# 13_Raspberry_Misc.net
KiCad netlist of a schematic drawn in Altium Designer
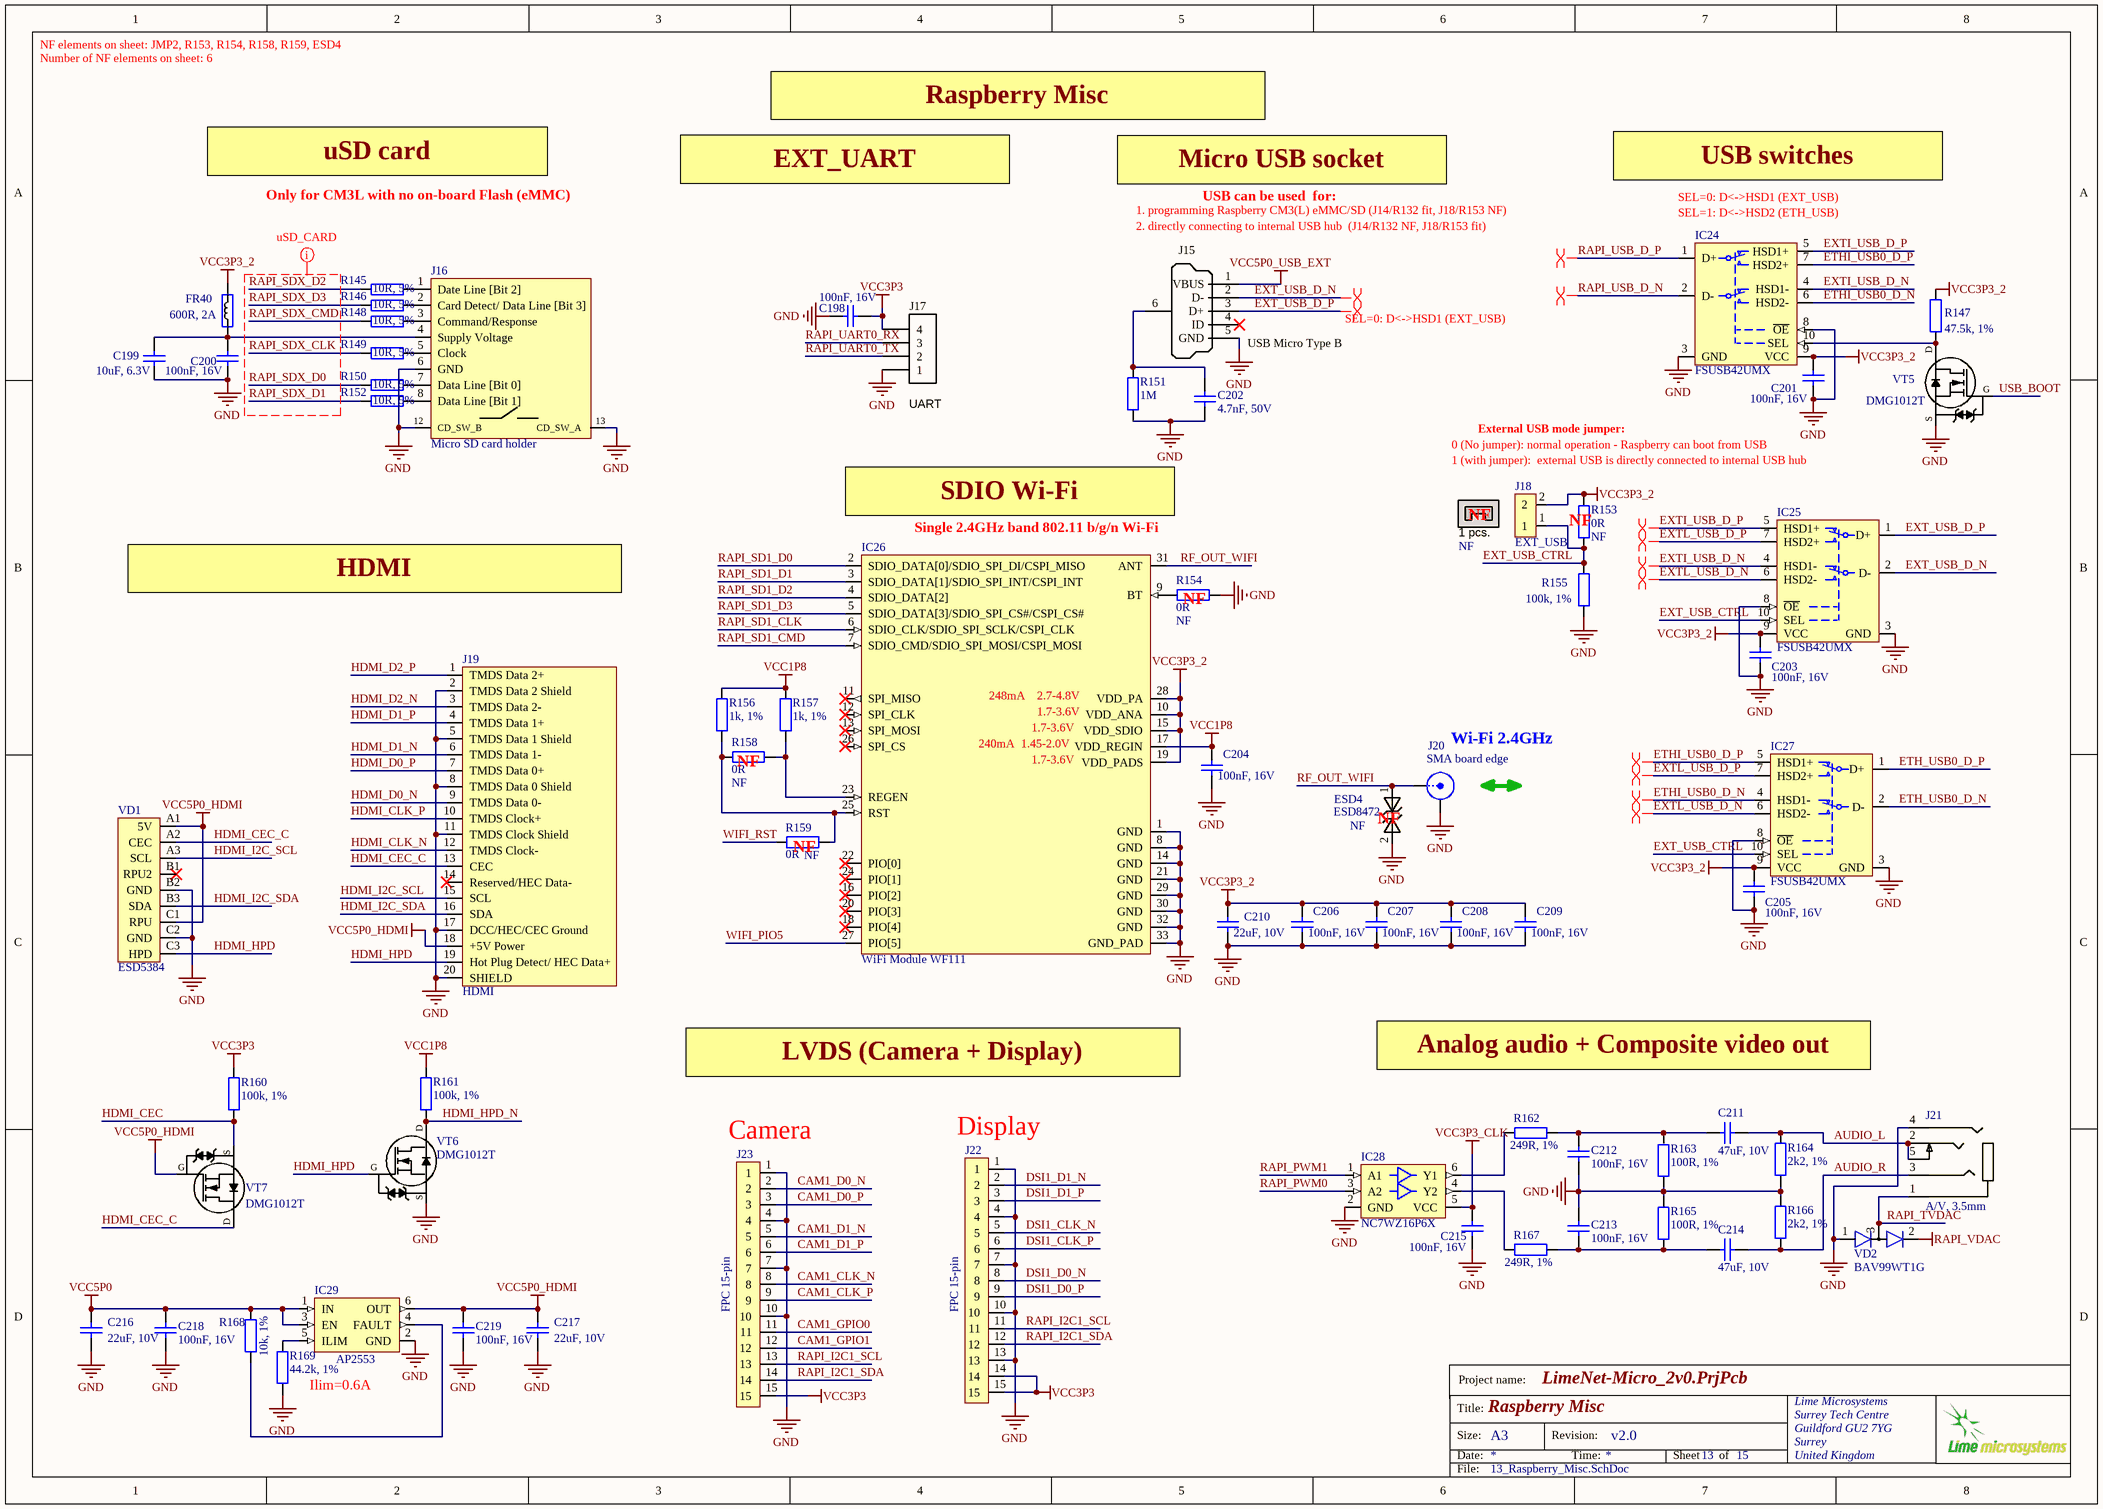
[diagram p0: 13_Raspberry_Misc.SchDoc]

(export (version "E")
  (design (tool "Eeschema 10.0.6"))
  (components
    (comp (ref "C198")
      (value "100nF, 16V")
      (footprint "CAP0402")
      (fields (field (name "TOLERANCE") "10 %") (field (name "MANUFACTURER") "Murata Electronics"))
      (libsource (lib "LimeFPGAboard_schLib") (part "Cap_0603"))
    )
    (comp (ref "C199")
      (value "10uF, 6.3V")
      (footprint "CAP0603")
      (fields (field (name "TOLERANCE") "±20%") (field (name "MANUFACTURER") "Yageo"))
      (libsource (lib "LimeFPGAboard_schLib") (part "Cap_0603"))
    )
    (comp (ref "C200")
      (value "100nF, 16V")
      (footprint "CAP0402")
      (fields (field (name "TOLERANCE") "10 %") (field (name "MANUFACTURER") "Murata Electronics"))
      (libsource (lib "LimeFPGAboard_schLib") (part "Cap_0603"))
    )
    (comp (ref "C201")
      (value "100nF, 16V")
      (footprint "CAP0402")
      (fields
        (field (name "MANUFACTURER") "Murata Electronics")
        (field (name "TOLERANCE") "10 %")
        (field (name "MANUFACTURER PART NUMBER") "GRM155R71C104KA88D")
      )
      (libsource (lib "LimeMicroAltiumLib_schLib") (part "Cap_0402"))
    )
    (comp (ref "C202")
      (value "4.7nF, 50V")
      (footprint "CAP0402")
      (fields
        (field (name "TOLERANCE") "±10%")
        (field (name "MANUFACTURER") "Murata Electronics North America")
      )
      (libsource (lib "LimeMicroAltiumLib_schLib") (part "Cap_0402"))
    )
    (comp (ref "C203")
      (value "100nF, 16V")
      (footprint "CAP0402")
      (fields
        (field (name "MANUFACTURER") "Murata Electronics")
        (field (name "TOLERANCE") "10 %")
        (field (name "MANUFACTURER PART NUMBER") "GRM155R71C104KA88D")
      )
      (libsource (lib "LimeMicroAltiumLib_schLib") (part "Cap_0402"))
    )
    (comp (ref "C204")
      (value "100nF, 16V")
      (footprint "CAP0402")
      (fields
        (field (name "MANUFACTURER") "Murata Electronics")
        (field (name "TOLERANCE") "10 %")
        (field (name "MANUFACTURER PART NUMBER") "GRM155R71C104KA88D")
      )
      (libsource (lib "LimeMicroAltiumLib_schLib") (part "Cap_0402"))
    )
    (comp (ref "C205")
      (value "100nF, 16V")
      (footprint "CAP0402")
      (fields
        (field (name "MANUFACTURER") "Murata Electronics")
        (field (name "TOLERANCE") "10 %")
        (field (name "MANUFACTURER PART NUMBER") "GRM155R71C104KA88D")
      )
      (libsource (lib "LimeMicroAltiumLib_schLib") (part "Cap_0402"))
    )
    (comp (ref "C206")
      (value "100nF, 16V")
      (footprint "CAP0402")
      (fields
        (field (name "MANUFACTURER") "Murata Electronics")
        (field (name "TOLERANCE") "10 %")
        (field (name "MANUFACTURER PART NUMBER") "GRM155R71C104KA88D")
      )
      (libsource (lib "LimeMicroAltiumLib_schLib") (part "Cap_0402"))
    )
    (comp (ref "C207")
      (value "100nF, 16V")
      (footprint "CAP0402")
      (fields
        (field (name "MANUFACTURER") "Murata Electronics")
        (field (name "TOLERANCE") "10 %")
        (field (name "MANUFACTURER PART NUMBER") "GRM155R71C104KA88D")
      )
      (libsource (lib "LimeMicroAltiumLib_schLib") (part "Cap_0402"))
    )
    (comp (ref "C208")
      (value "100nF, 16V")
      (footprint "CAP0402")
      (fields
        (field (name "MANUFACTURER") "Murata Electronics")
        (field (name "TOLERANCE") "10 %")
        (field (name "MANUFACTURER PART NUMBER") "GRM155R71C104KA88D")
      )
      (libsource (lib "LimeMicroAltiumLib_schLib") (part "Cap_0402"))
    )
    (comp (ref "C209")
      (value "100nF, 16V")
      (footprint "CAP0402")
      (fields
        (field (name "MANUFACTURER") "Murata Electronics")
        (field (name "TOLERANCE") "10 %")
        (field (name "MANUFACTURER PART NUMBER") "GRM155R71C104KA88D")
      )
      (libsource (lib "LimeMicroAltiumLib_schLib") (part "Cap_0402"))
    )
    (comp (ref "C210")
      (value "22uF, 10V")
      (footprint "CAP0603")
      (fields (field (name "TOLERANCE") "20 %") (field (name "MANUFACTURER") "TDK Corporation"))
      (libsource (lib "LimeFPGAboard_schLib") (part "Cap_0603"))
    )
    (comp (ref "C211")
      (value "47uF, 10V")
      (footprint "CAP1206")
      (fields (field (name "TOLERANCE") "±20%") (field (name "MANUFACTURER") "TDK Corporation"))
      (libsource (lib "LimeFPGAboard_schLib") (part "Cap_1206"))
    )
    (comp (ref "C212")
      (value "100nF, 16V")
      (footprint "CAP0402")
      (fields
        (field (name "MANUFACTURER") "Murata Electronics")
        (field (name "TOLERANCE") "10 %")
        (field (name "MANUFACTURER PART NUMBER") "GRM155R71C104KA88D")
      )
      (libsource (lib "LimeMicroAltiumLib_schLib") (part "Cap_0402"))
    )
    (comp (ref "C213")
      (value "100nF, 16V")
      (footprint "CAP0402")
      (fields
        (field (name "MANUFACTURER") "Murata Electronics")
        (field (name "TOLERANCE") "10 %")
        (field (name "MANUFACTURER PART NUMBER") "GRM155R71C104KA88D")
      )
      (libsource (lib "LimeMicroAltiumLib_schLib") (part "Cap_0402"))
    )
    (comp (ref "C214")
      (value "47uF, 10V")
      (footprint "CAP1206")
      (fields (field (name "TOLERANCE") "±20%") (field (name "MANUFACTURER") "TDK Corporation"))
      (libsource (lib "LimeFPGAboard_schLib") (part "Cap_1206"))
    )
    (comp (ref "C215")
      (value "100nF, 16V")
      (footprint "CAP0402")
      (fields
        (field (name "MANUFACTURER") "Murata Electronics")
        (field (name "TOLERANCE") "10 %")
        (field (name "MANUFACTURER PART NUMBER") "GRM155R71C104KA88D")
      )
      (libsource (lib "LimeMicroAltiumLib_schLib") (part "Cap_0402"))
    )
    (comp (ref "C216")
      (value "22uF, 10V")
      (footprint "CAP0603")
      (fields (field (name "TOLERANCE") "20 %") (field (name "MANUFACTURER") "TDK Corporation"))
      (libsource (lib "LimeFPGAboard_schLib") (part "Cap_0603"))
    )
    (comp (ref "C217")
      (value "22uF, 10V")
      (footprint "CAP0603")
      (fields (field (name "TOLERANCE") "20 %") (field (name "MANUFACTURER") "TDK Corporation"))
      (libsource (lib "LimeFPGAboard_schLib") (part "Cap_0603"))
    )
    (comp (ref "C218")
      (value "100nF, 16V")
      (footprint "CAP0402")
      (fields
        (field (name "MANUFACTURER") "Murata Electronics")
        (field (name "TOLERANCE") "10 %")
        (field (name "MANUFACTURER PART NUMBER") "GRM155R71C104KA88D")
      )
      (libsource (lib "LimeMicroAltiumLib_schLib") (part "Cap_0402"))
    )
    (comp (ref "C219")
      (value "100nF, 16V")
      (footprint "CAP0402")
      (fields
        (field (name "MANUFACTURER") "Murata Electronics")
        (field (name "TOLERANCE") "10 %")
        (field (name "MANUFACTURER PART NUMBER") "GRM155R71C104KA88D")
      )
      (libsource (lib "LimeMicroAltiumLib_schLib") (part "Cap_0402"))
    )
    (comp (ref "ESD4")
      (value "ESD8472")
      (footprint "ESD8472_X3DFN2")
      (fields
        (field (name "MANUFACTURER") "ON Semiconductor")
        (field (name "MANUFACTURER PART NUMBER") "ESD8472MUT5G")
        (field (name "ASSEMBLY INFO") "NF")
      )
      (libsource (lib "LimeMicroAltiumLib_schLib") (part "ESD8472"))
    )
    (comp (ref "FR40")
      (value "600R, 2A")
      (footprint "RES0805")
      (fields (field (name "MANUFACTURER") "TDK Corporation"))
      (libsource (lib "LimeMicroAltiumLib_schLib") (part "Ferrite"))
    )
    (comp (ref "IC24")
      (value "FSUSB42UMX")
      (footprint "FSUSB42UMX")
      (fields (field (name "MANUFACTURER") "ON Semiconductor") (field (name "BASE PART NUMBER") "FSUSB42"))
      (libsource (lib "LimeMicroAltiumLib_schLib_r01") (part "FSUSB42UMX"))
    )
    (comp (ref "IC25")
      (value "FSUSB42UMX")
      (footprint "FSUSB42UMX")
      (fields (field (name "MANUFACTURER") "ON Semiconductor") (field (name "BASE PART NUMBER") "FSUSB42"))
      (libsource (lib "") (part "FSUSB42UMX_1"))
    )
    (comp (ref "IC26")
      (value "WiFi Module WF111")
      (footprint "WF111-A-V1_WIFI")
      (fields (field (name "MANUFACTURER") "Bluegiga Technologies"))
      (libsource (lib "LimeMicroAltiumLib_schLib_r01") (part "WF111-A-V1_WIFI"))
    )
    (comp (ref "IC27")
      (value "FSUSB42UMX")
      (footprint "FSUSB42UMX")
      (fields (field (name "MANUFACTURER") "ON Semiconductor") (field (name "BASE PART NUMBER") "FSUSB42"))
      (libsource (lib "") (part "FSUSB42UMX_1"))
    )
    (comp (ref "IC28")
      (value "NC7WZ16P6X")
      (footprint "SC-70_NC7WZ16P6X")
      (fields (field (name "MANUFACTURER") "ON Semiconductor / Fairchild"))
      (libsource (lib "LimeMicroAltiumLib_schLib_r01") (part "NC7WZ16P6X_DUAL_BUFFER"))
    )
    (comp (ref "IC29")
      (value "AP2553")
      (footprint "SOT23-6")
      (fields (field (name "MANUFACTURER") "Diodes") (field (name "VOLTAGE") "5.5V"))
      (libsource (lib "LimeMicroAltiumLib_schLib_r01") (part "AP2553W6-7"))
    )
    (comp (ref "J15")
      (value "USB Micro Type B")
      (footprint "microUSB_v2")
      (description "Connector SMD USB Micro Type B")
      (fields (field (name "MANUFACTURER") "Amphenol FCI"))
      (libsource (lib "LimeMicroAltiumLib_schLib") (part "USB_Micro_TypeB"))
    )
    (comp (ref "J16")
      (value "Micro SD card holder")
      (footprint "MICRO_SD_CARD_114-00841-68_v2")
      (fields
        (field (name "MANUFACTURER") "Amphenol Commercial Products")
        (field (name "MANUFACTURER PART NUMBER") "114-00841-68")
      )
      (libsource (lib "LimeMicroAltiumLib_schLib_r01") (part "MICRO_SD_114-00841-68"))
    )
    (comp (ref "J17")
      (value "UART")
      (footprint "HEADER4X1_TH")
      (description "Header, 4-pin")
      (fields
        (field (name "MANUFACTURER") "Wurth Electronics Inc.")
        (field (name "MANUFACTURER PART NUMBER") "61300411121")
      )
      (libsource (lib "LimeMicroAltiumLib_schLib") (part "Header4P"))
    )
    (comp (ref "J18")
      (value "EXT_USB")
      (footprint "HDR_1x2")
      (fields (field (name "MANUFACTURER") "3M"))
      (libsource (lib "LimeFPGAboard_schLib") (part "Jumper"))
    )
    (comp (ref "J19")
      (value "HDMI")
      (footprint "HDMI_AMPHENOL_10029449-111RLF")
      (fields (field (name "MANUFACTURER") "Amphenol FCI"))
      (libsource (lib "LimeMicroAltiumLib_schLib_r01") (part "HDMI_AMPHENOL_10029449-111RLF"))
    )
    (comp (ref "J20")
      (value "SMA board edge")
      (footprint "SMA_connector_board_edge_SM")
      (description "CONN SMA JACK STR 50OHM EDGE MNT")
      (fields (field (name "MANUFACTURER") "RF Solutions"))
      (libsource (lib "LimeMicroAltiumLib_schLib") (part "RF_IF_connector"))
    )
    (comp (ref "J21")
      (value "A/V, 3.5mm")
      (footprint "Audio_jack_3.5mm")
      (fields (field (name "MANUFACTURER") "CUI Inc.") (field (name "MANUFACTURER PART NUMBER") "SJ-43515TS"))
      (libsource (lib "LimeMicroAltiumLib_schLib_r01") (part "AUDIO_JACK_3mm5_SJ-4351X"))
    )
    (comp (ref "J22")
      (value "FPC 15-pin")
      (footprint "FPC_CONNECTOR_15pin_1-1734248-5")
      (fields (field (name "MANUFACTURER") "TE Connectivity"))
      (libsource (lib "LimeMicroAltiumLib_schLib_r01") (part "FPC_CONNECTOR_15pin_1-1734248-5"))
    )
    (comp (ref "J23")
      (value "FPC 15-pin")
      (footprint "FPC_CONNECTOR_15pin_1-1734248-5")
      (fields (field (name "MANUFACTURER") "TE Connectivity"))
      (libsource (lib "LimeMicroAltiumLib_schLib_r01") (part "FPC_CONNECTOR_15pin_1-1734248-5"))
    )
    (comp (ref "JMP2")
      (value "1 pcs.")
      (description "Shorting Jumper, 2-position, 1.27mm pitch")
      (fields (field (name "ASSEMBLY INFO") "NF") (field (name "MANUFACTURER") "Sullins"))
      (libsource (lib "LimeMicroAltiumLib_schLib") (part "JUMP_2P_CONN_HEADER"))
    )
    (comp (ref "R145")
      (value "10R, 5%")
      (footprint "RES0402")
      (fields (field (name "TOLERANCE") "±5%") (field (name "MANUFACTURER") "Yageo"))
      (libsource (lib "LimeMicroAltiumLib_schLib") (part "Res_0402"))
    )
    (comp (ref "R146")
      (value "10R, 5%")
      (footprint "RES0402")
      (fields (field (name "TOLERANCE") "±5%") (field (name "MANUFACTURER") "Yageo"))
      (libsource (lib "LimeMicroAltiumLib_schLib") (part "Res_0402"))
    )
    (comp (ref "R147")
      (value "47.5k, 1%")
      (footprint "RES0402")
      (fields
        (field (name "MANUFACTURER PART NUMBER") "RC0402FR-0747K5L")
        (field (name "TOLERANCE") "±1%")
        (field (name "MANUFACTURER") "Yageo")
      )
      (libsource (lib "LimeMicroAltiumLib_schLib") (part "Res_0402"))
    )
    (comp (ref "R148")
      (value "10R, 5%")
      (footprint "RES0402")
      (fields (field (name "TOLERANCE") "±5%") (field (name "MANUFACTURER") "Yageo"))
      (libsource (lib "LimeMicroAltiumLib_schLib") (part "Res_0402"))
    )
    (comp (ref "R149")
      (value "10R, 5%")
      (footprint "RES0402")
      (fields (field (name "TOLERANCE") "±5%") (field (name "MANUFACTURER") "Yageo"))
      (libsource (lib "LimeMicroAltiumLib_schLib") (part "Res_0402"))
    )
    (comp (ref "R150")
      (value "10R, 5%")
      (footprint "RES0402")
      (fields (field (name "TOLERANCE") "±5%") (field (name "MANUFACTURER") "Yageo"))
      (libsource (lib "LimeMicroAltiumLib_schLib") (part "Res_0402"))
    )
    (comp (ref "R151")
      (value "1M")
      (footprint "RES0402")
      (fields (field (name "MANUFACTURER") "TE CONNECTIVITY"))
      (libsource (lib "LimeMicroAltiumLib_schLib") (part "Res_0402"))
    )
    (comp (ref "R152")
      (value "10R, 5%")
      (footprint "RES0402")
      (fields (field (name "TOLERANCE") "±5%") (field (name "MANUFACTURER") "Yageo"))
      (libsource (lib "LimeMicroAltiumLib_schLib") (part "Res_0402"))
    )
    (comp (ref "R153")
      (value "0R")
      (footprint "RES0402")
      (fields
        (field (name "ASSEMBLY INFO") "NF")
        (field (name "MANUFACTURER") "Yageo")
        (field (name "TOLERANCE") "Jumper")
      )
      (libsource (lib "LimeMicroAltiumLib_schLib") (part "Res_0402"))
    )
    (comp (ref "R154")
      (value "0R")
      (footprint "RES0402")
      (fields
        (field (name "ASSEMBLY INFO") "NF")
        (field (name "MANUFACTURER") "Yageo")
        (field (name "TOLERANCE") "Jumper")
      )
      (libsource (lib "LimeMicroAltiumLib_schLib") (part "Res_0402"))
    )
    (comp (ref "R155")
      (value "100k, 1%")
      (footprint "RES0402")
      (fields
        (field (name "MANUFACTURER") "Vishay Dale")
        (field (name "TOLERANCE") "±1%")
        (field (name "MANUFACTURER PART NUMBER") "CRCW0402100KFKEDC")
      )
      (libsource (lib "LimeMicroAltiumLib_schLib") (part "Res_0402"))
    )
    (comp (ref "R156")
      (value "1k, 1%")
      (footprint "RES0402")
      (fields (field (name "MANUFACTURER") "Stackpole Electronics Inc") (field (name "TOLERANCE") "±1%"))
      (libsource (lib "LimeMicroAltiumLib_schLib") (part "Res_0402"))
    )
    (comp (ref "R157")
      (value "1k, 1%")
      (footprint "RES0402")
      (fields (field (name "MANUFACTURER") "Stackpole Electronics Inc") (field (name "TOLERANCE") "±1%"))
      (libsource (lib "LimeMicroAltiumLib_schLib") (part "Res_0402"))
    )
    (comp (ref "R158")
      (value "0R")
      (footprint "RES0402")
      (fields
        (field (name "ASSEMBLY INFO") "NF")
        (field (name "MANUFACTURER") "Yageo")
        (field (name "TOLERANCE") "Jumper")
      )
      (libsource (lib "LimeMicroAltiumLib_schLib") (part "Res_0402"))
    )
    (comp (ref "R159")
      (value "0R")
      (footprint "RES0402")
      (fields
        (field (name "ASSEMBLY INFO") "NF")
        (field (name "MANUFACTURER") "Yageo")
        (field (name "TOLERANCE") "Jumper")
      )
      (libsource (lib "LimeMicroAltiumLib_schLib") (part "Res_0402"))
    )
    (comp (ref "R160")
      (value "100k, 1%")
      (footprint "RES0402")
      (fields
        (field (name "MANUFACTURER") "Vishay Dale")
        (field (name "TOLERANCE") "±1%")
        (field (name "MANUFACTURER PART NUMBER") "CRCW0402100KFKEDC")
      )
      (libsource (lib "LimeMicroAltiumLib_schLib") (part "Res_0402"))
    )
    (comp (ref "R161")
      (value "100k, 1%")
      (footprint "RES0402")
      (fields
        (field (name "MANUFACTURER") "Vishay Dale")
        (field (name "TOLERANCE") "±1%")
        (field (name "MANUFACTURER PART NUMBER") "CRCW0402100KFKEDC")
      )
      (libsource (lib "LimeMicroAltiumLib_schLib") (part "Res_0402"))
    )
    (comp (ref "R162")
      (value "249R, 1%")
      (footprint "RES0402")
      (fields (field (name "MANUFACTURER") "Stackpole Electronics Inc") (field (name "TOLERANCE") "±1%"))
      (libsource (lib "LimeMicroAltiumLib_schLib") (part "Res_0402"))
    )
    (comp (ref "R163")
      (value "100R, 1%")
      (footprint "RES0402")
      (fields (field (name "TOLERANCE") "±1%") (field (name "MANUFACTURER") "Stackpole Electronics Inc."))
      (libsource (lib "LimeMicroAltiumLib_schLib") (part "Res_0402"))
    )
    (comp (ref "R164")
      (value "2k2, 1%")
      (footprint "RES0402")
      (fields (field (name "MANUFACTURER") "Stackpole Electronics Inc") (field (name "TOLERANCE") "±1%"))
      (libsource (lib "LimeMicroAltiumLib_schLib") (part "Res_0402"))
    )
    (comp (ref "R165")
      (value "100R, 1%")
      (footprint "RES0402")
      (fields (field (name "TOLERANCE") "±1%") (field (name "MANUFACTURER") "Stackpole Electronics Inc."))
      (libsource (lib "LimeMicroAltiumLib_schLib") (part "Res_0402"))
    )
    (comp (ref "R166")
      (value "2k2, 1%")
      (footprint "RES0402")
      (fields (field (name "MANUFACTURER") "Stackpole Electronics Inc") (field (name "TOLERANCE") "±1%"))
      (libsource (lib "LimeMicroAltiumLib_schLib") (part "Res_0402"))
    )
    (comp (ref "R167")
      (value "249R, 1%")
      (footprint "RES0402")
      (fields (field (name "MANUFACTURER") "Stackpole Electronics Inc") (field (name "TOLERANCE") "±1%"))
      (libsource (lib "LimeMicroAltiumLib_schLib") (part "Res_0402"))
    )
    (comp (ref "R168")
      (value "10k, 1%")
      (footprint "RES0402")
      (fields (field (name "MANUFACTURER") "Yageo") (field (name "TOLERANCE") "±1%"))
      (libsource (lib "LimeMicroAltiumLib_schLib") (part "Res_0402"))
    )
    (comp (ref "R169")
      (value "44.2k, 1%")
      (footprint "RES0402")
      (fields
        (field (name "TOLERANCE") "±1%")
        (field (name "MANUFACTURER") "Panasonic Electronic Components")
      )
      (libsource (lib "LimeMicroAltiumLib_schLib") (part "Res_0402"))
    )
    (comp (ref "VD1")
      (value "ESD5384")
      (footprint "TVS_ESD5384NCTBG")
      (fields (field (name "MANUFACTURER") "ON Semiconductor"))
      (libsource (lib "LimeMicroAltiumLib_schLib_r01") (part "TVS_ESD5384NCTBG"))
    )
    (comp (ref "VD2")
      (value "BAV99WT1G")
      (footprint "SC-70_BAV99WT1G")
      (fields (field (name "MANUFACTURER") "ON Semiconductor"))
      (libsource (lib "LimeMicroAltiumLib_schLib_r01") (part "BAV99WT1G_DUAL_DIODE"))
    )
    (comp (ref "VT5")
      (value "DMG1012T")
      (footprint "SOT523")
      (fields
        (field (name "MANUFACTURER") "Diodes Incorporated")
        (field (name "MANUFACTURER PART NUMBER") "DMG1012TQ-7")
      )
      (libsource (lib "LimeMicroAltiumLib_schLib_r01") (part "DMG1012T"))
    )
    (comp (ref "VT6")
      (value "DMG1012T")
      (footprint "SOT523")
      (fields
        (field (name "MANUFACTURER") "Diodes Incorporated")
        (field (name "MANUFACTURER PART NUMBER") "DMG1012TQ-7")
      )
      (libsource (lib "LimeMicroAltiumLib_schLib_r01") (part "DMG1012T"))
    )
    (comp (ref "VT7")
      (value "DMG1012T")
      (footprint "SOT523")
      (fields
        (field (name "MANUFACTURER") "Diodes Incorporated")
        (field (name "MANUFACTURER PART NUMBER") "DMG1012TQ-7")
      )
      (libsource (lib "LimeMicroAltiumLib_schLib_r01") (part "DMG1012T"))
    )
  )
  (nets
    (net (code "1") (name "/AUDIO_L") (class "Default")
      (node (ref "C211") (pin "1") (pinfunction "1_1") (pintype "passive"))
      (node (ref "J21") (pin "2") (pinfunction "2_2") (pintype "passive"))
      (node (ref "J21") (pin "5") (pinfunction "5_5") (pintype "passive"))
      (node (ref "R164") (pin "1") (pinfunction "1_1") (pintype "passive"))
    )
    (net (code "2") (name "/AUDIO_R") (class "Default")
      (node (ref "C214") (pin "1") (pinfunction "1_1") (pintype "passive"))
      (node (ref "J21") (pin "3") (pinfunction "3_3") (pintype "passive"))
      (node (ref "R166") (pin "2") (pinfunction "2_2") (pintype "passive"))
    )
    (net (code "3") (name "/CAM1_CLK_N") (class "Default")
      (node (ref "J23") (pin "8") (pinfunction "8_8") (pintype "passive"))
    )
    (net (code "4") (name "/CAM1_CLK_P") (class "Default")
      (node (ref "J23") (pin "9") (pinfunction "9_9") (pintype "passive"))
    )
    (net (code "5") (name "/CAM1_D0_N") (class "Default")
      (node (ref "J23") (pin "2") (pinfunction "2_2") (pintype "passive"))
    )
    (net (code "6") (name "/CAM1_D0_P") (class "Default")
      (node (ref "J23") (pin "3") (pinfunction "3_3") (pintype "passive"))
    )
    (net (code "7") (name "/CAM1_D1_N") (class "Default")
      (node (ref "J23") (pin "5") (pinfunction "5_5") (pintype "passive"))
    )
    (net (code "8") (name "/CAM1_D1_P") (class "Default")
      (node (ref "J23") (pin "6") (pinfunction "6_6") (pintype "passive"))
    )
    (net (code "9") (name "/CAM1_GPIO0") (class "Default")
      (node (ref "J23") (pin "11") (pinfunction "11_11") (pintype "passive"))
    )
    (net (code "10") (name "/CAM1_GPIO1") (class "Default")
      (node (ref "J23") (pin "12") (pinfunction "12_12") (pintype "passive"))
    )
    (net (code "11") (name "/DSI1_CLK_N") (class "Default")
      (node (ref "J22") (pin "5") (pinfunction "5_5") (pintype "passive"))
    )
    (net (code "12") (name "/DSI1_CLK_P") (class "Default")
      (node (ref "J22") (pin "6") (pinfunction "6_6") (pintype "passive"))
    )
    (net (code "13") (name "/DSI1_D0_N") (class "Default")
      (node (ref "J22") (pin "8") (pinfunction "8_8") (pintype "passive"))
    )
    (net (code "14") (name "/DSI1_D0_P") (class "Default")
      (node (ref "J22") (pin "9") (pinfunction "9_9") (pintype "passive"))
    )
    (net (code "15") (name "/DSI1_D1_N") (class "Default")
      (node (ref "J22") (pin "2") (pinfunction "2_2") (pintype "passive"))
    )
    (net (code "16") (name "/DSI1_D1_P") (class "Default")
      (node (ref "J22") (pin "3") (pinfunction "3_3") (pintype "passive"))
    )
    (net (code "17") (name "/ETHI_USB0_D_N") (class "Default")
      (node (ref "IC24") (pin "6") (pinfunction "HSD2-_6") (pintype "passive"))
      (node (ref "IC27") (pin "4") (pinfunction "HSD1-_4") (pintype "passive"))
    )
    (net (code "18") (name "/ETHI_USB0_D_P") (class "Default")
      (node (ref "IC24") (pin "7") (pinfunction "HSD2+_7") (pintype "passive"))
      (node (ref "IC27") (pin "5") (pinfunction "HSD1+_5") (pintype "passive"))
    )
    (net (code "19") (name "/ETH_USB0_D_N") (class "Default")
      (node (ref "IC27") (pin "2") (pinfunction "D-_2") (pintype "passive"))
    )
    (net (code "20") (name "/ETH_USB0_D_P") (class "Default")
      (node (ref "IC27") (pin "1") (pinfunction "D+_1") (pintype "passive"))
    )
    (net (code "21") (name "/EXTI_USB_D_N") (class "Default")
      (node (ref "IC24") (pin "4") (pinfunction "HSD1-_4") (pintype "passive"))
      (node (ref "IC25") (pin "4") (pinfunction "HSD1-_4") (pintype "passive"))
    )
    (net (code "22") (name "/EXTI_USB_D_P") (class "Default")
      (node (ref "IC24") (pin "5") (pinfunction "HSD1+_5") (pintype "passive"))
      (node (ref "IC25") (pin "5") (pinfunction "HSD1+_5") (pintype "passive"))
    )
    (net (code "23") (name "/EXTL_USB_D_N") (class "Default")
      (node (ref "IC25") (pin "6") (pinfunction "HSD2-_6") (pintype "passive"))
      (node (ref "IC27") (pin "6") (pinfunction "HSD2-_6") (pintype "passive"))
    )
    (net (code "24") (name "/EXTL_USB_D_P") (class "Default")
      (node (ref "IC25") (pin "7") (pinfunction "HSD2+_7") (pintype "passive"))
      (node (ref "IC27") (pin "7") (pinfunction "HSD2+_7") (pintype "passive"))
    )
    (net (code "25") (name "/EXT_USB_CTRL") (class "Default")
      (node (ref "IC25") (pin "10") (pinfunction "SEL_10") (pintype "input"))
      (node (ref "IC27") (pin "10") (pinfunction "SEL_10") (pintype "input"))
      (node (ref "J18") (pin "1") (pinfunction "1_1") (pintype "passive"))
      (node (ref "R153") (pin "1") (pinfunction "1_1") (pintype "passive"))
      (node (ref "R155") (pin "1") (pinfunction "1_1") (pintype "passive"))
    )
    (net (code "26") (name "/EXT_USB_D_N") (class "Default")
      (node (ref "IC25") (pin "2") (pinfunction "D-_2") (pintype "passive"))
      (node (ref "J15") (pin "2") (pinfunction "D-_2") (pintype "passive"))
    )
    (net (code "27") (name "/EXT_USB_D_P") (class "Default")
      (node (ref "IC25") (pin "1") (pinfunction "D+_1") (pintype "passive"))
      (node (ref "J15") (pin "3") (pinfunction "D+_3") (pintype "passive"))
    )
    (net (code "28") (name "/HDMI_CEC") (class "Default")
      (node (ref "R160") (pin "2") (pinfunction "2_2") (pintype "passive"))
      (node (ref "VT7") (pin "S") (pinfunction "S_S") (pintype "passive"))
    )
    (net (code "29") (name "/HDMI_CEC_C") (class "Default")
      (node (ref "J19") (pin "13") (pinfunction "CEC_13") (pintype "passive"))
      (node (ref "VD1") (pin "A2") (pinfunction "CEC_A2") (pintype "passive"))
      (node (ref "VT7") (pin "D") (pinfunction "D_D") (pintype "passive"))
    )
    (net (code "30") (name "/HDMI_CLK_N") (class "Default")
      (node (ref "J19") (pin "12") (pinfunction "TMDS_Clock-_12") (pintype "passive"))
    )
    (net (code "31") (name "/HDMI_CLK_P") (class "Default")
      (node (ref "J19") (pin "10") (pinfunction "TMDS_Clock+_10") (pintype "passive"))
    )
    (net (code "32") (name "/HDMI_D0_N") (class "Default")
      (node (ref "J19") (pin "9") (pinfunction "TMDS_Data_0-_9") (pintype "passive"))
    )
    (net (code "33") (name "/HDMI_D0_P") (class "Default")
      (node (ref "J19") (pin "7") (pinfunction "TMDS_Data_0+_7") (pintype "passive"))
    )
    (net (code "34") (name "/HDMI_D1_N") (class "Default")
      (node (ref "J19") (pin "6") (pinfunction "TMDS_Data_1-_6") (pintype "passive"))
    )
    (net (code "35") (name "/HDMI_D1_P") (class "Default")
      (node (ref "J19") (pin "4") (pinfunction "TMDS_Data_1+_4") (pintype "passive"))
    )
    (net (code "36") (name "/HDMI_D2_N") (class "Default")
      (node (ref "J19") (pin "3") (pinfunction "TMDS_Data_2-_3") (pintype "passive"))
    )
    (net (code "37") (name "/HDMI_D2_P") (class "Default")
      (node (ref "J19") (pin "1") (pinfunction "TMDS_Data_2+_1") (pintype "passive"))
    )
    (net (code "38") (name "/HDMI_HPD") (class "Default")
      (node (ref "J19") (pin "19") (pinfunction "Hot_Plug_Detect/_HEC_Data+_19") (pintype "passive"))
      (node (ref "VD1") (pin "C3") (pinfunction "HPD_C3") (pintype "passive"))
      (node (ref "VT6") (pin "G") (pinfunction "G_G") (pintype "passive"))
    )
    (net (code "39") (name "/HDMI_HPD_N") (class "Default")
      (node (ref "R161") (pin "2") (pinfunction "2_2") (pintype "passive"))
      (node (ref "VT6") (pin "D") (pinfunction "D_D") (pintype "passive"))
    )
    (net (code "40") (name "/HDMI_I2C_SCL") (class "Default")
      (node (ref "J19") (pin "15") (pinfunction "SCL_15") (pintype "passive"))
      (node (ref "VD1") (pin "A3") (pinfunction "SCL_A3") (pintype "passive"))
    )
    (net (code "41") (name "/HDMI_I2C_SDA") (class "Default")
      (node (ref "J19") (pin "16") (pinfunction "SDA_16") (pintype "passive"))
      (node (ref "VD1") (pin "B3") (pinfunction "SDA_B3") (pintype "passive"))
    )
    (net (code "42") (name "/RAPI_I2C1_SCL") (class "Default")
      (node (ref "J22") (pin "11") (pinfunction "11_11") (pintype "passive"))
      (node (ref "J23") (pin "13") (pinfunction "13_13") (pintype "passive"))
    )
    (net (code "43") (name "/RAPI_I2C1_SDA") (class "Default")
      (node (ref "J22") (pin "12") (pinfunction "12_12") (pintype "passive"))
      (node (ref "J23") (pin "14") (pinfunction "14_14") (pintype "passive"))
    )
    (net (code "44") (name "/RAPI_PWM0") (class "Default")
      (node (ref "IC28") (pin "3") (pinfunction "A2_3") (pintype "input"))
    )
    (net (code "45") (name "/RAPI_PWM1") (class "Default")
      (node (ref "IC28") (pin "1") (pinfunction "A1_1") (pintype "input"))
    )
    (net (code "46") (name "/RAPI_SD1_CLK") (class "Default")
      (node (ref "IC26") (pin "6") (pinfunction "SDIO_CLK/SDIO_SPI_SCLK/CSPI_CLK_6") (pintype "input"))
    )
    (net (code "47") (name "/RAPI_SD1_CMD") (class "Default")
      (node (ref "IC26") (pin "7") (pinfunction "SDIO_CMD/SDIO_SPI_MOSI/CSPI_MOSI_7") (pintype "input"))
    )
    (net (code "48") (name "/RAPI_SD1_D0") (class "Default")
      (node (ref "IC26") (pin "2") (pinfunction "SDIO_DATA[0]/SDIO_SPI_DI/CSPI_MISO_2") (pintype "bidirectional"))
    )
    (net (code "49") (name "/RAPI_SD1_D1") (class "Default")
      (node (ref "IC26") (pin "3") (pinfunction "SDIO_DATA[1]/SDIO_SPI_INT/CSPI_INT_3") (pintype "bidirectional"))
    )
    (net (code "50") (name "/RAPI_SD1_D2") (class "Default")
      (node (ref "IC26") (pin "4") (pinfunction "SDIO_DATA[2]_4") (pintype "bidirectional"))
    )
    (net (code "51") (name "/RAPI_SD1_D3") (class "Default")
      (node (ref "IC26") (pin "5") (pinfunction "SDIO_DATA[3]/SDIO_SPI_CS#/CSPI_CS#_5") (pintype "bidirectional"))
    )
    (net (code "52") (name "/RAPI_SDX_CLK") (class "Default")
      (node (ref "R149") (pin "1") (pinfunction "1_1") (pintype "passive"))
    )
    (net (code "53") (name "/RAPI_SDX_CMD") (class "Default")
      (node (ref "R148") (pin "1") (pinfunction "1_1") (pintype "passive"))
    )
    (net (code "54") (name "/RAPI_SDX_D0") (class "Default")
      (node (ref "R150") (pin "1") (pinfunction "1_1") (pintype "passive"))
    )
    (net (code "55") (name "/RAPI_SDX_D1") (class "Default")
      (node (ref "R152") (pin "1") (pinfunction "1_1") (pintype "passive"))
    )
    (net (code "56") (name "/RAPI_SDX_D2") (class "Default")
      (node (ref "R145") (pin "1") (pinfunction "1_1") (pintype "passive"))
    )
    (net (code "57") (name "/RAPI_SDX_D3") (class "Default")
      (node (ref "R146") (pin "1") (pinfunction "1_1") (pintype "passive"))
    )
    (net (code "58") (name "/RAPI_TVDAC") (class "Default")
      (node (ref "J21") (pin "1") (pinfunction "1_1") (pintype "passive"))
      (node (ref "VD2") (pin "3") (pinfunction "3_3") (pintype "passive"))
    )
    (net (code "59") (name "/RAPI_UART0_RX") (class "Default")
      (node (ref "J17") (pin "3") (pinfunction "3_3") (pintype "passive"))
    )
    (net (code "60") (name "/RAPI_UART0_TX") (class "Default")
      (node (ref "J17") (pin "2") (pinfunction "2_2") (pintype "passive"))
    )
    (net (code "61") (name "/RAPI_USB_D_N") (class "Default")
      (node (ref "IC24") (pin "2") (pinfunction "D-_2") (pintype "passive"))
    )
    (net (code "62") (name "/RAPI_USB_D_P") (class "Default")
      (node (ref "IC24") (pin "1") (pinfunction "D+_1") (pintype "passive"))
    )
    (net (code "63") (name "/RF_OUT_WIFI") (class "Default")
      (node (ref "ESD4") (pin "1") (pinfunction "1_1") (pintype "passive"))
      (node (ref "IC26") (pin "31") (pinfunction "ANT_31") (pintype "passive"))
      (node (ref "J20") (pin "1") (pinfunction "X_1") (pintype "passive"))
    )
    (net (code "64") (name "/USB_BOOT") (class "Default")
      (node (ref "VT5") (pin "G") (pinfunction "G_G") (pintype "passive"))
    )
    (net (code "65") (name "/WIFI_PIO5") (class "Default")
      (node (ref "IC26") (pin "27") (pinfunction "PIO[5]_27") (pintype "bidirectional"))
    )
    (net (code "66") (name "/WIFI_RST") (class "Default")
      (node (ref "R159") (pin "1") (pinfunction "1_1") (pintype "passive"))
    )
    (net (code "67") (name "GND") (class "Default")
      (node (ref "C198") (pin "2") (pinfunction "2_2") (pintype "passive"))
      (node (ref "C199") (pin "1") (pinfunction "1_1") (pintype "passive"))
      (node (ref "C200") (pin "2") (pinfunction "2_2") (pintype "passive"))
      (node (ref "C201") (pin "2") (pinfunction "2_2") (pintype "passive"))
      (node (ref "C202") (pin "2") (pinfunction "2_2") (pintype "passive"))
      (node (ref "C203") (pin "2") (pinfunction "2_2") (pintype "passive"))
      (node (ref "C204") (pin "1") (pinfunction "1_1") (pintype "passive"))
      (node (ref "C205") (pin "2") (pinfunction "2_2") (pintype "passive"))
      (node (ref "C206") (pin "1") (pinfunction "1_1") (pintype "passive"))
      (node (ref "C207") (pin "1") (pinfunction "1_1") (pintype "passive"))
      (node (ref "C208") (pin "1") (pinfunction "1_1") (pintype "passive"))
      (node (ref "C209") (pin "1") (pinfunction "1_1") (pintype "passive"))
      (node (ref "C210") (pin "1") (pinfunction "1_1") (pintype "passive"))
      (node (ref "C212") (pin "2") (pinfunction "2_2") (pintype "passive"))
      (node (ref "C213") (pin "1") (pinfunction "1_1") (pintype "passive"))
      (node (ref "C215") (pin "2") (pinfunction "2_2") (pintype "passive"))
      (node (ref "C216") (pin "1") (pinfunction "1_1") (pintype "passive"))
      (node (ref "C217") (pin "1") (pinfunction "1_1") (pintype "passive"))
      (node (ref "C218") (pin "2") (pinfunction "2_2") (pintype "passive"))
      (node (ref "C219") (pin "2") (pinfunction "2_2") (pintype "passive"))
      (node (ref "ESD4") (pin "2") (pinfunction "2_2") (pintype "passive"))
      (node (ref "IC24") (pin "3") (pinfunction "GND_3") (pintype "passive"))
      (node (ref "IC24") (pin "8") (pinfunction "~{OE}_8") (pintype "input"))
      (node (ref "IC25") (pin "3") (pinfunction "GND_3") (pintype "passive"))
      (node (ref "IC25") (pin "8") (pinfunction "~{OE}_8") (pintype "input"))
      (node (ref "IC26") (pin "1") (pinfunction "GND_1") (pintype "passive"))
      (node (ref "IC26") (pin "14") (pinfunction "GND_14") (pintype "passive"))
      (node (ref "IC26") (pin "21") (pinfunction "GND_21") (pintype "passive"))
      (node (ref "IC26") (pin "29") (pinfunction "GND_29") (pintype "passive"))
      (node (ref "IC26") (pin "30") (pinfunction "GND_30") (pintype "passive"))
      (node (ref "IC26") (pin "32") (pinfunction "GND_32") (pintype "passive"))
      (node (ref "IC26") (pin "33") (pinfunction "GND_PAD_33") (pintype "passive"))
      (node (ref "IC26") (pin "8") (pinfunction "GND_8") (pintype "passive"))
      (node (ref "IC27") (pin "3") (pinfunction "GND_3") (pintype "passive"))
      (node (ref "IC27") (pin "8") (pinfunction "~{OE}_8") (pintype "input"))
      (node (ref "IC28") (pin "2") (pinfunction "GND_2") (pintype "passive"))
      (node (ref "IC29") (pin "2") (pinfunction "GND_2") (pintype "passive"))
      (node (ref "J15") (pin "5") (pinfunction "GND_5") (pintype "passive"))
      (node (ref "J16") (pin "12") (pinfunction "CD_SW_B_12") (pintype "passive"))
      (node (ref "J16") (pin "13") (pinfunction "CD_SW_A_13") (pintype "passive"))
      (node (ref "J16") (pin "6") (pinfunction "GND_6") (pintype "passive"))
      (node (ref "J17") (pin "1") (pinfunction "1_1") (pintype "passive"))
      (node (ref "J19") (pin "11") (pinfunction "TMDS_Clock_Shield_11") (pintype "passive"))
      (node (ref "J19") (pin "17") (pinfunction "DCC/HEC/CEC_Ground_17") (pintype "passive"))
      (node (ref "J19") (pin "2") (pinfunction "TMDS_Data_2_Shield_2") (pintype "passive"))
      (node (ref "J19") (pin "20") (pinfunction "SHIELD_20") (pintype "passive"))
      (node (ref "J19") (pin "5") (pinfunction "TMDS_Data_1_Shield_5") (pintype "passive"))
      (node (ref "J19") (pin "8") (pinfunction "TMDS_Data_0_Shield_8") (pintype "passive"))
      (node (ref "J20") (pin "2") (pinfunction "Y_2") (pintype "passive"))
      (node (ref "J21") (pin "4") (pinfunction "4_4") (pintype "passive"))
      (node (ref "J22") (pin "1") (pinfunction "1_1") (pintype "passive"))
      (node (ref "J22") (pin "10") (pinfunction "10_10") (pintype "passive"))
      (node (ref "J22") (pin "13") (pinfunction "13_13") (pintype "passive"))
      (node (ref "J22") (pin "4") (pinfunction "4_4") (pintype "passive"))
      (node (ref "J22") (pin "7") (pinfunction "7_7") (pintype "passive"))
      (node (ref "J23") (pin "1") (pinfunction "1_1") (pintype "passive"))
      (node (ref "J23") (pin "10") (pinfunction "10_10") (pintype "passive"))
      (node (ref "J23") (pin "4") (pinfunction "4_4") (pintype "passive"))
      (node (ref "J23") (pin "7") (pinfunction "7_7") (pintype "passive"))
      (node (ref "R151") (pin "2") (pinfunction "2_2") (pintype "passive"))
      (node (ref "R154") (pin "2") (pinfunction "2_2") (pintype "passive"))
      (node (ref "R155") (pin "2") (pinfunction "2_2") (pintype "passive"))
      (node (ref "R163") (pin "1") (pinfunction "1_1") (pintype "passive"))
      (node (ref "R164") (pin "2") (pinfunction "2_2") (pintype "passive"))
      (node (ref "R165") (pin "2") (pinfunction "2_2") (pintype "passive"))
      (node (ref "R166") (pin "1") (pinfunction "1_1") (pintype "passive"))
      (node (ref "R169") (pin "2") (pinfunction "2_2") (pintype "passive"))
      (node (ref "VD1") (pin "B2") (pinfunction "GND_B2") (pintype "passive"))
      (node (ref "VD1") (pin "C2") (pinfunction "GND_C2") (pintype "passive"))
      (node (ref "VD2") (pin "1") (pinfunction "1_1") (pintype "passive"))
      (node (ref "VT5") (pin "S") (pinfunction "S_S") (pintype "passive"))
      (node (ref "VT6") (pin "S") (pinfunction "S_S") (pintype "passive"))
    )
    (net (code "68") (name "Net-(C211-Pad2)") (class "Default")
      (node (ref "C211") (pin "2") (pinfunction "2_2") (pintype "passive"))
      (node (ref "C212") (pin "1") (pinfunction "1_1") (pintype "passive"))
      (node (ref "R162") (pin "2") (pinfunction "2_2") (pintype "passive"))
      (node (ref "R163") (pin "2") (pinfunction "2_2") (pintype "passive"))
    )
    (net (code "69") (name "Net-(C213-Pad2)") (class "Default")
      (node (ref "C213") (pin "2") (pinfunction "2_2") (pintype "passive"))
      (node (ref "C214") (pin "2") (pinfunction "2_2") (pintype "passive"))
      (node (ref "R165") (pin "1") (pinfunction "1_1") (pintype "passive"))
      (node (ref "R167") (pin "2") (pinfunction "2_2") (pintype "passive"))
    )
    (net (code "70") (name "Net-(IC24-SEL)") (class "Default")
      (node (ref "IC24") (pin "10") (pinfunction "SEL_10") (pintype "input"))
      (node (ref "R147") (pin "2") (pinfunction "2_2") (pintype "passive"))
      (node (ref "VT5") (pin "D") (pinfunction "D_D") (pintype "passive"))
    )
    (net (code "71") (name "Net-(IC26-BT)") (class "Default")
      (node (ref "IC26") (pin "9") (pinfunction "BT_9") (pintype "input"))
      (node (ref "R154") (pin "1") (pinfunction "1_1") (pintype "passive"))
    )
    (net (code "72") (name "Net-(IC26-REGEN)") (class "Default")
      (node (ref "IC26") (pin "23") (pinfunction "REGEN_23") (pintype "input"))
      (node (ref "R157") (pin "2") (pinfunction "2_2") (pintype "passive"))
      (node (ref "R158") (pin "2") (pinfunction "2_2") (pintype "passive"))
    )
    (net (code "73") (name "Net-(IC26-RST)") (class "Default")
      (node (ref "IC26") (pin "25") (pinfunction "RST_25") (pintype "input"))
      (node (ref "R156") (pin "2") (pinfunction "2_2") (pintype "passive"))
      (node (ref "R158") (pin "1") (pinfunction "1_1") (pintype "passive"))
      (node (ref "R159") (pin "2") (pinfunction "2_2") (pintype "passive"))
    )
    (net (code "74") (name "Net-(IC28-Y1)") (class "Default")
      (node (ref "IC28") (pin "6") (pinfunction "Y1_6") (pintype "output"))
      (node (ref "R162") (pin "1") (pinfunction "1_1") (pintype "passive"))
    )
    (net (code "75") (name "Net-(IC28-Y2)") (class "Default")
      (node (ref "IC28") (pin "4") (pinfunction "Y2_4") (pintype "output"))
      (node (ref "R167") (pin "1") (pinfunction "1_1") (pintype "passive"))
    )
    (net (code "76") (name "Net-(IC29-FAULT)") (class "Default")
      (node (ref "IC29") (pin "4") (pinfunction "FAULT_4") (pintype "output"))
      (node (ref "R168") (pin "2") (pinfunction "2_2") (pintype "passive"))
    )
    (net (code "77") (name "Net-(IC29-ILIM)") (class "Default")
      (node (ref "IC29") (pin "5") (pinfunction "ILIM_5") (pintype "input"))
      (node (ref "R169") (pin "1") (pinfunction "1_1") (pintype "passive"))
    )
    (net (code "78") (name "Net-(J15-Shell)") (class "Default")
      (node (ref "C202") (pin "1") (pinfunction "1_1") (pintype "passive"))
      (node (ref "J15") (pin "6") (pinfunction "Shell_6") (pintype "passive"))
      (node (ref "R151") (pin "1") (pinfunction "1_1") (pintype "passive"))
    )
    (net (code "79") (name "Net-(J16-Card_Detect{slash}_Data_Line_[Bit_3])") (class "Default")
      (node (ref "J16") (pin "2") (pinfunction "Card_Detect/_Data_Line_[Bit_3]_2") (pintype "passive"))
      (node (ref "R146") (pin "2") (pinfunction "2_2") (pintype "passive"))
    )
    (net (code "80") (name "Net-(J16-Clock)") (class "Default")
      (node (ref "J16") (pin "5") (pinfunction "Clock_5") (pintype "passive"))
      (node (ref "R149") (pin "2") (pinfunction "2_2") (pintype "passive"))
    )
    (net (code "81") (name "Net-(J16-Command{slash}Response)") (class "Default")
      (node (ref "J16") (pin "3") (pinfunction "Command/Response_3") (pintype "passive"))
      (node (ref "R148") (pin "2") (pinfunction "2_2") (pintype "passive"))
    )
    (net (code "82") (name "Net-(J16-Data_Line_[Bit_0])") (class "Default")
      (node (ref "J16") (pin "7") (pinfunction "Data_Line_[Bit_0]_7") (pintype "passive"))
      (node (ref "R150") (pin "2") (pinfunction "2_2") (pintype "passive"))
    )
    (net (code "83") (name "Net-(J16-Data_Line_[Bit_1])") (class "Default")
      (node (ref "J16") (pin "8") (pinfunction "Data_Line_[Bit_1]_8") (pintype "passive"))
      (node (ref "R152") (pin "2") (pinfunction "2_2") (pintype "passive"))
    )
    (net (code "84") (name "Net-(J16-Date_Line_[Bit_2])") (class "Default")
      (node (ref "J16") (pin "1") (pinfunction "Date_Line_[Bit_2]_1") (pintype "passive"))
      (node (ref "R145") (pin "2") (pinfunction "2_2") (pintype "passive"))
    )
    (net (code "85") (name "Net-(J16-Supply_Voltage)") (class "Default")
      (node (ref "C199") (pin "2") (pinfunction "2_2") (pintype "passive"))
      (node (ref "C200") (pin "1") (pinfunction "1_1") (pintype "passive"))
      (node (ref "FR40") (pin "1") (pinfunction "1_1") (pintype "passive"))
      (node (ref "J16") (pin "4") (pinfunction "Supply_Voltage_4") (pintype "passive"))
    )
    (net (code "86") (name "RAPI_VDAC") (class "Default")
      (node (ref "VD2") (pin "2") (pinfunction "2_2") (pintype "passive"))
    )
    (net (code "87") (name "VCC1P8") (class "Default")
      (node (ref "C204") (pin "2") (pinfunction "2_2") (pintype "passive"))
      (node (ref "IC26") (pin "17") (pinfunction "VDD_REGIN_17") (pintype "passive"))
      (node (ref "R156") (pin "1") (pinfunction "1_1") (pintype "passive"))
      (node (ref "R157") (pin "1") (pinfunction "1_1") (pintype "passive"))
      (node (ref "R161") (pin "1") (pinfunction "1_1") (pintype "passive"))
    )
    (net (code "88") (name "VCC3P3") (class "Default")
      (node (ref "C198") (pin "1") (pinfunction "1_1") (pintype "passive"))
      (node (ref "J17") (pin "4") (pinfunction "4_4") (pintype "passive"))
      (node (ref "J22") (pin "14") (pinfunction "14_14") (pintype "passive"))
      (node (ref "J22") (pin "15") (pinfunction "15_15") (pintype "passive"))
      (node (ref "J23") (pin "15") (pinfunction "15_15") (pintype "passive"))
      (node (ref "R160") (pin "1") (pinfunction "1_1") (pintype "passive"))
    )
    (net (code "89") (name "VCC3P3_2") (class "Default")
      (node (ref "C201") (pin "1") (pinfunction "1_1") (pintype "passive"))
      (node (ref "C203") (pin "1") (pinfunction "1_1") (pintype "passive"))
      (node (ref "C205") (pin "1") (pinfunction "1_1") (pintype "passive"))
      (node (ref "C206") (pin "2") (pinfunction "2_2") (pintype "passive"))
      (node (ref "C207") (pin "2") (pinfunction "2_2") (pintype "passive"))
      (node (ref "C208") (pin "2") (pinfunction "2_2") (pintype "passive"))
      (node (ref "C209") (pin "2") (pinfunction "2_2") (pintype "passive"))
      (node (ref "C210") (pin "2") (pinfunction "2_2") (pintype "passive"))
      (node (ref "FR40") (pin "2") (pinfunction "2_2") (pintype "passive"))
      (node (ref "IC24") (pin "9") (pinfunction "VCC_9") (pintype "power_in"))
      (node (ref "IC25") (pin "9") (pinfunction "VCC_9") (pintype "power_in"))
      (node (ref "IC26") (pin "10") (pinfunction "VDD_ANA_10") (pintype "power_in"))
      (node (ref "IC26") (pin "15") (pinfunction "VDD_SDIO_15") (pintype "power_in"))
      (node (ref "IC26") (pin "19") (pinfunction "VDD_PADS_19") (pintype "power_in"))
      (node (ref "IC26") (pin "28") (pinfunction "VDD_PA_28") (pintype "power_in"))
      (node (ref "IC27") (pin "9") (pinfunction "VCC_9") (pintype "power_in"))
      (node (ref "J18") (pin "2") (pinfunction "2_2") (pintype "passive"))
      (node (ref "R147") (pin "1") (pinfunction "1_1") (pintype "passive"))
      (node (ref "R153") (pin "2") (pinfunction "2_2") (pintype "passive"))
    )
    (net (code "90") (name "VCC3P3_CLK") (class "Default")
      (node (ref "C215") (pin "1") (pinfunction "1_1") (pintype "passive"))
      (node (ref "IC28") (pin "5") (pinfunction "VCC_5") (pintype "power_in"))
    )
    (net (code "91") (name "VCC5P0") (class "Default")
      (node (ref "C216") (pin "2") (pinfunction "2_2") (pintype "passive"))
      (node (ref "C218") (pin "1") (pinfunction "1_1") (pintype "passive"))
      (node (ref "IC29") (pin "1") (pinfunction "IN_1") (pintype "input"))
      (node (ref "IC29") (pin "3") (pinfunction "EN_3") (pintype "input"))
      (node (ref "R168") (pin "1") (pinfunction "1_1") (pintype "passive"))
    )
    (net (code "92") (name "VCC5P0_HDMI") (class "Default")
      (node (ref "C217") (pin "2") (pinfunction "2_2") (pintype "passive"))
      (node (ref "C219") (pin "1") (pinfunction "1_1") (pintype "passive"))
      (node (ref "IC29") (pin "6") (pinfunction "OUT_6") (pintype "output"))
      (node (ref "J19") (pin "18") (pinfunction "+5V_Power_18") (pintype "passive"))
      (node (ref "VD1") (pin "A1") (pinfunction "5V_A1") (pintype "passive"))
      (node (ref "VD1") (pin "C1") (pinfunction "RPU_C1") (pintype "passive"))
      (node (ref "VT7") (pin "G") (pinfunction "G_G") (pintype "passive"))
    )
    (net (code "93") (name "VCC5P0_USB_EXT") (class "Default")
      (node (ref "J15") (pin "1") (pinfunction "VBUS_1") (pintype "passive"))
    )
    (net (code "94") (name "unconnected-(IC26-PIO[0]-Pad22)") (class "Default")
      (node (ref "IC26") (pin "22") (pinfunction "PIO[0]_22") (pintype "bidirectional+no_connect"))
    )
    (net (code "95") (name "unconnected-(IC26-PIO[1]-Pad24)") (class "Default")
      (node (ref "IC26") (pin "24") (pinfunction "PIO[1]_24") (pintype "bidirectional+no_connect"))
    )
    (net (code "96") (name "unconnected-(IC26-PIO[2]-Pad16)") (class "Default")
      (node (ref "IC26") (pin "16") (pinfunction "PIO[2]_16") (pintype "bidirectional+no_connect"))
    )
    (net (code "97") (name "unconnected-(IC26-PIO[3]-Pad20)") (class "Default")
      (node (ref "IC26") (pin "20") (pinfunction "PIO[3]_20") (pintype "bidirectional+no_connect"))
    )
    (net (code "98") (name "unconnected-(IC26-PIO[4]-Pad18)") (class "Default")
      (node (ref "IC26") (pin "18") (pinfunction "PIO[4]_18") (pintype "bidirectional+no_connect"))
    )
    (net (code "99") (name "unconnected-(IC26-SPI_CLK-Pad12)") (class "Default")
      (node (ref "IC26") (pin "12") (pinfunction "SPI_CLK_12") (pintype "input+no_connect"))
    )
    (net (code "100") (name "unconnected-(IC26-SPI_CS-Pad26)") (class "Default")
      (node (ref "IC26") (pin "26") (pinfunction "SPI_CS_26") (pintype "input+no_connect"))
    )
    (net (code "101") (name "unconnected-(IC26-SPI_MISO-Pad11)") (class "Default")
      (node (ref "IC26") (pin "11") (pinfunction "SPI_MISO_11") (pintype "output+no_connect"))
    )
    (net (code "102") (name "unconnected-(IC26-SPI_MOSI-Pad13)") (class "Default")
      (node (ref "IC26") (pin "13") (pinfunction "SPI_MOSI_13") (pintype "input+no_connect"))
    )
    (net (code "103") (name "unconnected-(J15-ID-Pad4)") (class "Default")
      (node (ref "J15") (pin "4") (pinfunction "ID_4") (pintype "passive+no_connect"))
    )
    (net (code "104") (name "unconnected-(J19-Reserved{slash}HEC_Data--Pad14)") (class "Default")
      (node (ref "J19") (pin "14") (pinfunction "Reserved/HEC_Data-_14") (pintype "passive+no_connect"))
    )
    (net (code "105") (name "unconnected-(JMP2-Pad1)") (class "Default")
      (node (ref "JMP2") (pin "1") (pinfunction "1_1") (pintype "passive"))
    )
    (net (code "106") (name "unconnected-(JMP2-Pad2)") (class "Default")
      (node (ref "JMP2") (pin "2") (pinfunction "2_2") (pintype "passive"))
    )
    (net (code "107") (name "unconnected-(VD1-RPU2-PadB1)") (class "Default")
      (node (ref "VD1") (pin "B1") (pinfunction "RPU2_B1") (pintype "passive+no_connect"))
    )
  )
)
